# SAU-G0_sheet1.net
KiCad netlist of a schematic drawn in Altium Designer
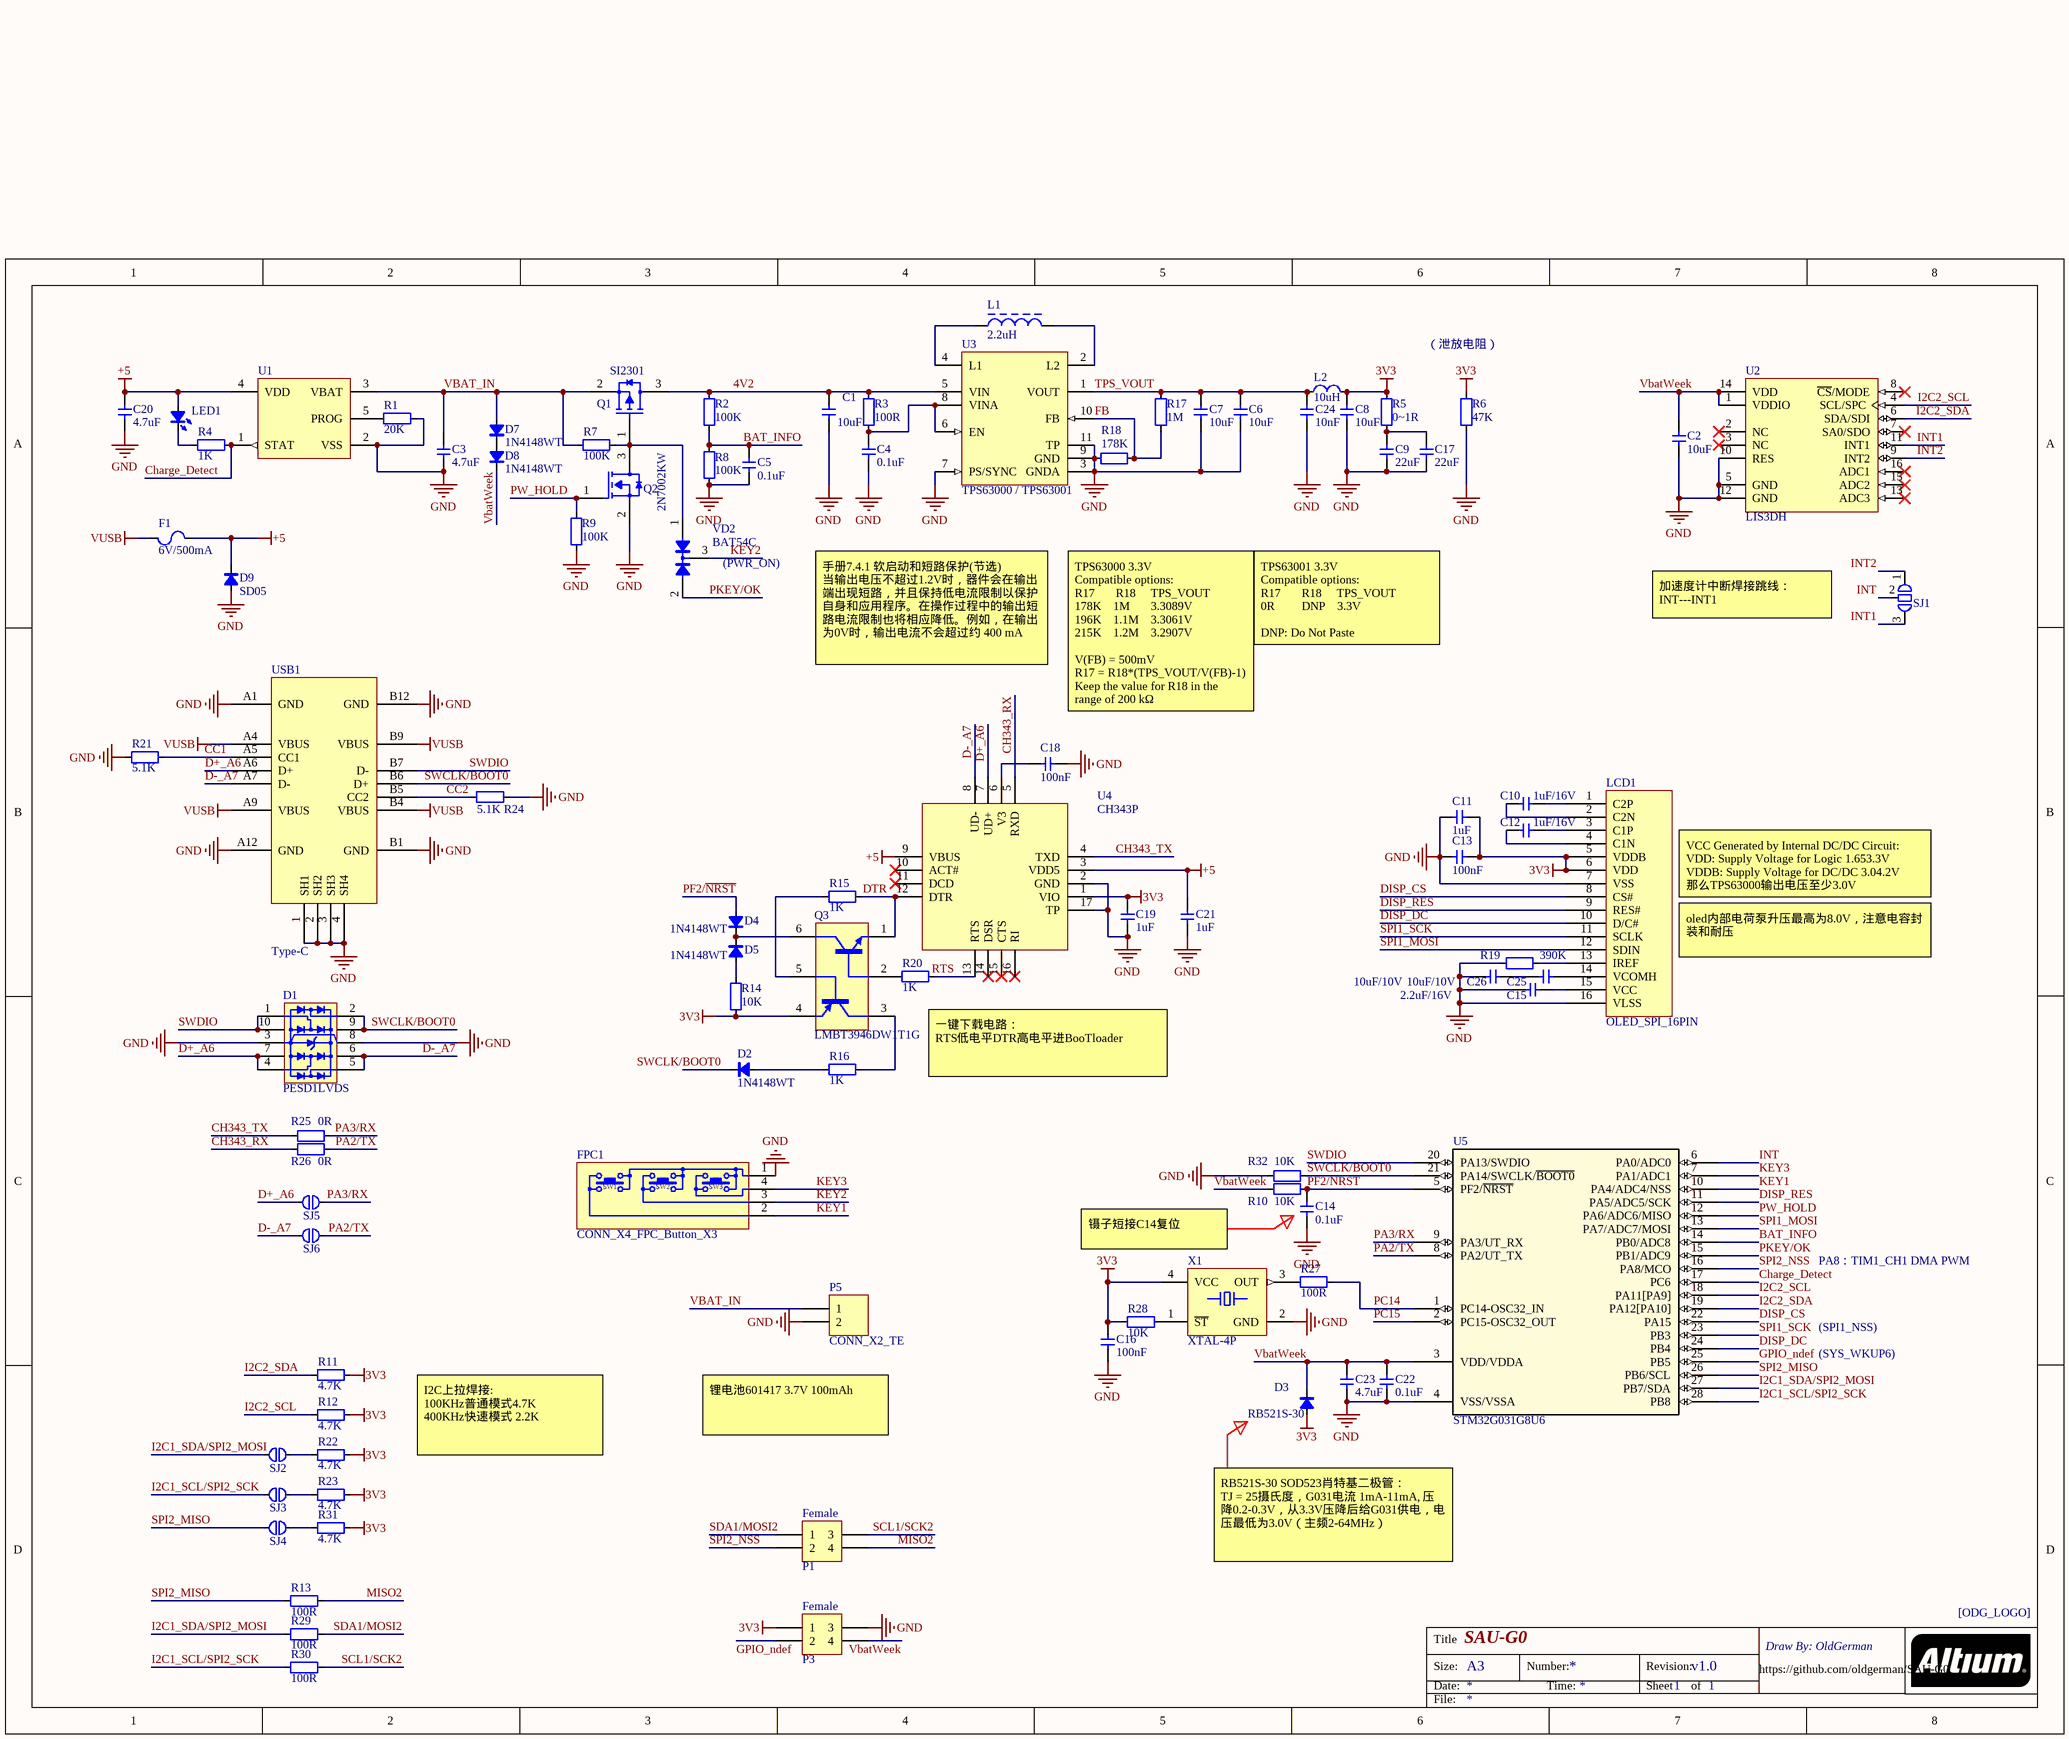
[diagram p0: SAU-G0_sheet1.SchDoc]

(export (version "E")
  (design (tool "Eeschema 10.0.6"))
  (components
    (comp (ref "C1")
      (value "10uF")
      (footprint "C0402")
      (description "Capacitor")
      (libsource (lib "ODG_AD_Lib") (part "CAP"))
    )
    (comp (ref "C2")
      (value "10uF")
      (footprint "C0402")
      (description "Capacitor")
      (libsource (lib "ODG_AD_Lib") (part "CAP"))
    )
    (comp (ref "C3")
      (value "4.7uF")
      (footprint "C0603")
      (description "Capacitor")
      (libsource (lib "ODG_AD_Lib") (part "CAP"))
    )
    (comp (ref "C4")
      (value "0.1uF")
      (footprint "C0402")
      (description "Capacitor")
      (libsource (lib "ODG_AD_Lib") (part "CAP"))
    )
    (comp (ref "C5")
      (value "0.1uF")
      (footprint "C0402")
      (description "Capacitor")
      (libsource (lib "ODG_AD_Lib") (part "CAP"))
    )
    (comp (ref "C6")
      (value "10uF")
      (footprint "C0402")
      (description "Capacitor")
      (libsource (lib "ODG_AD_Lib") (part "CAP"))
    )
    (comp (ref "C7")
      (value "10uF")
      (footprint "C0402")
      (description "Capacitor")
      (libsource (lib "ODG_AD_Lib") (part "CAP"))
    )
    (comp (ref "C8")
      (value "10uF")
      (footprint "C0402")
      (description "Capacitor")
      (libsource (lib "ODG_AD_Lib") (part "CAP"))
    )
    (comp (ref "C9")
      (value "22uF")
      (footprint "C0603")
      (description "Capacitor")
      (libsource (lib "ODG_AD_Lib") (part "CAP"))
    )
    (comp (ref "C10")
      (value "1uF/16V")
      (footprint "C0402")
      (description "Capacitor")
      (libsource (lib "ODG_AD_Lib") (part "CAP"))
    )
    (comp (ref "C11")
      (value "1uF")
      (footprint "C0402")
      (description "Capacitor")
      (libsource (lib "ODG_AD_Lib") (part "CAP"))
    )
    (comp (ref "C12")
      (value "1uF/16V")
      (footprint "C0402")
      (description "Capacitor")
      (libsource (lib "ODG_AD_Lib") (part "CAP"))
    )
    (comp (ref "C13")
      (value "100nF")
      (footprint "C0402")
      (description "Capacitor")
      (libsource (lib "ODG_AD_Lib") (part "CAP"))
    )
    (comp (ref "C14")
      (value "0.1uF")
      (footprint "C0402")
      (description "Capacitor")
      (libsource (lib "ODG_AD_Lib") (part "CAP"))
    )
    (comp (ref "C15")
      (value "2.2uF/16V")
      (footprint "C0603")
      (description "Capacitor")
      (libsource (lib "ODG_AD_Lib") (part "CAP"))
    )
    (comp (ref "C16")
      (value "100nF")
      (footprint "C0402")
      (description "Capacitor")
      (libsource (lib "ODG_AD_Lib") (part "CAP"))
    )
    (comp (ref "C17")
      (value "22uF")
      (footprint "C0603")
      (description "Capacitor")
      (libsource (lib "ODG_AD_Lib") (part "CAP"))
    )
    (comp (ref "C18")
      (value "100nF")
      (footprint "C0402")
      (description "Capacitor")
      (libsource (lib "ODG_AD_Lib") (part "CAP"))
    )
    (comp (ref "C19")
      (value "1uF")
      (footprint "C0402")
      (description "Capacitor")
      (libsource (lib "ODG_AD_Lib") (part "CAP"))
    )
    (comp (ref "C20")
      (value "4.7uF")
      (footprint "C0603")
      (description "Capacitor")
      (libsource (lib "ODG_AD_Lib") (part "CAP"))
    )
    (comp (ref "C21")
      (value "1uF")
      (footprint "C0402")
      (description "Capacitor")
      (libsource (lib "ODG_AD_Lib") (part "CAP"))
    )
    (comp (ref "C22")
      (value "0.1uF")
      (footprint "C0402")
      (description "Capacitor")
      (libsource (lib "ODG_AD_Lib") (part "CAP"))
    )
    (comp (ref "C23")
      (value "4.7uF")
      (footprint "C0402")
      (description "Capacitor")
      (libsource (lib "ODG_AD_Lib") (part "CAP"))
    )
    (comp (ref "C24")
      (value "10nF")
      (footprint "C0402")
      (description "Capacitor")
      (libsource (lib "ODG_AD_Lib") (part "CAP"))
    )
    (comp (ref "C25")
      (value "10uF/10V")
      (footprint "C0402")
      (description "Capacitor")
      (libsource (lib "ODG_AD_Lib") (part "CAP"))
    )
    (comp (ref "C26")
      (value "10uF/10V")
      (footprint "C0402")
      (description "Capacitor")
      (libsource (lib "ODG_AD_Lib") (part "CAP"))
    )
    (comp (ref "D1")
      (value "PESD1LVDS")
      (footprint "DFN2510-10_SOT1165-1")
      (description "Ultra-Low Capacitance TVS Protection")
      (fields (field (name "版权归属") "源创客"))
      (libsource (lib "ODG_AD_Lib") (part "PESD1LVDS"))
    )
    (comp (ref "D2")
      (value "1N4148WT")
      (footprint "SOD-523")
      (description "二极管")
      (libsource (lib "") (part "DIODE_2"))
    )
    (comp (ref "D3")
      (value "RB521S-30")
      (footprint "SOD-523")
      (description "二极管")
      (libsource (lib "") (part "DIODE_1"))
    )
    (comp (ref "D4")
      (value "1N4148WT")
      (footprint "SOD-523")
      (description "二极管")
      (libsource (lib "ODG_AD_Lib") (part "DIODE"))
    )
    (comp (ref "D5")
      (value "1N4148WT")
      (footprint "SOD-523")
      (description "二极管")
      (libsource (lib "") (part "DIODE_3"))
    )
    (comp (ref "D7")
      (value "1N4148WT")
      (footprint "SOD-523")
      (description "二极管")
      (libsource (lib "ODG_AD_Lib") (part "DIODE"))
    )
    (comp (ref "D8")
      (value "1N4148WT")
      (footprint "SOD-523")
      (description "二极管")
      (libsource (lib "ODG_AD_Lib") (part "DIODE"))
    )
    (comp (ref "D9")
      (value "SD05")
      (footprint "SOD-323")
      (description "单向 5V TVS")
      (libsource (lib "") (part "DIODE_1"))
    )
    (comp (ref "F1")
      (value "6V/500mA")
      (footprint "FUSE0603_0.5MM")
      (description "贴片自恢复保险丝")
      (libsource (lib "ODG_AD_Lib") (part "FUSE"))
    )
    (comp (ref "FPC1")
      (value "CONN_X4_FPC_Button_X3")
      (footprint "FPC_Buttons_X3_Flip_to_PCB_Buttom_to_Back_3.06mm_NO_3D_NO_SLIK_1")
      (description "豆老板1.6元车G031电子烟拆机的玩意儿")
      (libsource (lib "ODG_AD_Lib") (part "CONN_X4_FPC_Button_X3"))
    )
    (comp (ref "L1")
      (value "2.2uH")
      (footprint "TAIYO YUDEN MAMK2520T1R0M")
      (libsource (lib "ODG_nRLC_Project") (part "Inductor"))
    )
    (comp (ref "L2")
      (value "10uH")
      (footprint "FER0603")
      (description "贴片叠层电感")
      (libsource (lib "ODG_AD_Lib") (part "inductor_mini"))
    )
    (comp (ref "LCD1")
      (value "OLED_SPI_16PIN")
      (footprint "oled_64x48_0.66_SSD1306_TOP_FPC_to_BACK_1mm_NO_3D_NO_SLIK_1")
      (libsource (lib "ODG_AD_Lib") (part "OLED_SPI_16PIN"))
    )
    (comp (ref "LED1") (value "LED") (footprint "LED0603_WHITE") (libsource (lib "ODG_AD_Lib") (part "LED")))
    (comp (ref "ODG4")
      (value "ODG_LOGO")
      (footprint "ODG_LOGO")
      (libsource (lib "ODG_AD_Lib") (part "ODG_LOGO"))
    )
    (comp (ref "P1")
      (value "Female")
      (footprint "2.0mm_Fmale_2x2")
      (libsource (lib "ODG_AD_Lib") (part "CONN_2X2"))
    )
    (comp (ref "P3")
      (value "Female")
      (footprint "2.0mm_Fmale_2x2")
      (libsource (lib "ODG_AD_Lib") (part "CONN_2X2"))
    )
    (comp (ref "P5")
      (value "CONN_X2_TE")
      (footprint "TE-198181x_Female+Male")
      (description "泰科1981812-1\r\n泰科1981813-1\r\n使用32AWG 特氟龙线外径0.38mm\r\n刺破式")
      (libsource (lib "ODG_AD_Lib") (part "CONN_X2_TE"))
    )
    (comp (ref "Q1")
      (value "SI2301")
      (footprint "INFINEON SOT-23-3")
      (description "P-MOS")
      (libsource (lib "ODG_AD_Lib") (part "P-MOS_123"))
    )
    (comp (ref "Q2")
      (value "2N7002KW")
      (footprint "DIODES SOT-323-3")
      (description "N-MOS")
      (libsource (lib "ODG_AD_Lib") (part "N-MOS_123"))
    )
    (comp (ref "Q3")
      (value "LMBT3946DW1T1G")
      (footprint "ON SEMI SOT-363")
      (description "PNP+NPN, SOT-363")
      (libsource (lib "ODG_AD_Lib") (part "LMBT3946DW1T1G"))
    )
    (comp (ref "R1")
      (value "20K")
      (footprint "R0402")
      (description "Resistor")
      (libsource (lib "") (part "RES_3"))
    )
    (comp (ref "R2")
      (value "100K")
      (footprint "R0402")
      (description "Resistor")
      (libsource (lib "ODG_AD_Lib") (part "RES"))
    )
    (comp (ref "R3")
      (value "100R")
      (footprint "R0402")
      (description "Resistor")
      (libsource (lib "ODG_AD_Lib") (part "RES"))
    )
    (comp (ref "R4")
      (value "1K")
      (footprint "R0402")
      (description "Resistor")
      (libsource (lib "") (part "RES_3"))
    )
    (comp (ref "R5")
      (value "0~1R")
      (footprint "R0402")
      (description "Resistor")
      (libsource (lib "ODG_AD_Lib") (part "RES"))
    )
    (comp (ref "R6")
      (value "47K")
      (footprint "R0603")
      (description "Resistor")
      (libsource (lib "ODG_AD_Lib") (part "RES"))
    )
    (comp (ref "R7")
      (value "100K")
      (footprint "R0402")
      (description "Resistor")
      (libsource (lib "") (part "RES_3"))
    )
    (comp (ref "R8")
      (value "100K")
      (footprint "R0402")
      (description "Resistor")
      (libsource (lib "ODG_AD_Lib") (part "RES"))
    )
    (comp (ref "R9")
      (value "100K")
      (footprint "R0402")
      (description "Resistor")
      (libsource (lib "ODG_AD_Lib") (part "RES"))
    )
    (comp (ref "R10")
      (value "10K")
      (footprint "R0402")
      (description "Resistor")
      (libsource (lib "") (part "RES_2"))
    )
    (comp (ref "R11")
      (value "4.7K")
      (footprint "R0402")
      (description "Resistor")
      (libsource (lib "") (part "RES_2"))
    )
    (comp (ref "R12")
      (value "4.7K")
      (footprint "R0402")
      (description "Resistor")
      (libsource (lib "") (part "RES_2"))
    )
    (comp (ref "R13")
      (value "100R")
      (footprint "R0402")
      (description "Resistor")
      (libsource (lib "") (part "RES_2"))
    )
    (comp (ref "R14")
      (value "10K")
      (footprint "R0402")
      (description "Resistor")
      (libsource (lib "") (part "RES_1"))
    )
    (comp (ref "R15")
      (value "1K")
      (footprint "R0402")
      (description "Resistor")
      (libsource (lib "ODG_AD_Lib") (part "RES"))
    )
    (comp (ref "R16")
      (value "1K")
      (footprint "R0402")
      (description "Resistor")
      (libsource (lib "ODG_AD_Lib") (part "RES"))
    )
    (comp (ref "R17")
      (value "1M")
      (footprint "R0402")
      (description "Resistor")
      (libsource (lib "ODG_AD_Lib") (part "RES"))
    )
    (comp (ref "R18")
      (value "178K")
      (footprint "R0402")
      (description "Resistor")
      (libsource (lib "") (part "RES_3"))
    )
    (comp (ref "R19")
      (value "390K")
      (footprint "R0402")
      (description "Resistor")
      (libsource (lib "") (part "RES_1"))
    )
    (comp (ref "R20")
      (value "1K")
      (footprint "R0402")
      (description "Resistor")
      (libsource (lib "") (part "RES_2"))
    )
    (comp (ref "R21")
      (value "5.1K")
      (footprint "R0402")
      (description "Resistor")
      (libsource (lib "") (part "RES_3"))
    )
    (comp (ref "R22")
      (value "4.7K")
      (footprint "R0402")
      (description "Resistor")
      (libsource (lib "") (part "RES_2"))
    )
    (comp (ref "R23")
      (value "4.7K")
      (footprint "R0402")
      (description "Resistor")
      (libsource (lib "") (part "RES_2"))
    )
    (comp (ref "R24")
      (value "5.1K")
      (footprint "R0402")
      (description "Resistor")
      (libsource (lib "") (part "RES_2"))
    )
    (comp (ref "R25")
      (value "0R")
      (footprint "R0402")
      (description "Resistor")
      (libsource (lib "") (part "RES_1"))
    )
    (comp (ref "R26")
      (value "0R")
      (footprint "R0402")
      (description "Resistor")
      (libsource (lib "") (part "RES_1"))
    )
    (comp (ref "R27")
      (value "100R")
      (footprint "R0402")
      (description "Resistor")
      (libsource (lib "") (part "RES_2"))
    )
    (comp (ref "R28")
      (value "10K")
      (footprint "R0402")
      (description "Resistor")
      (libsource (lib "") (part "RES_2"))
    )
    (comp (ref "R29")
      (value "100R")
      (footprint "R0402")
      (description "Resistor")
      (libsource (lib "") (part "RES_2"))
    )
    (comp (ref "R30")
      (value "100R")
      (footprint "R0402")
      (description "Resistor")
      (libsource (lib "") (part "RES_2"))
    )
    (comp (ref "R31")
      (value "4.7K")
      (footprint "R0402")
      (description "Resistor")
      (libsource (lib "") (part "RES_2"))
    )
    (comp (ref "R32")
      (value "10K")
      (footprint "R0402")
      (description "Resistor")
      (libsource (lib "ODG_AD_Lib") (part "RES"))
    )
    (comp (ref "SJ1")
      (value "SJ_3P")
      (footprint "SJ_3P_MINI")
      (description "焊接跳线二选一")
      (libsource (lib "ODG_AD_Lib") (part "SJ_3P"))
    )
    (comp (ref "SJ2")
      (value "SJ_2P")
      (footprint "SJ_2P_TINY")
      (description "焊接跳线")
      (libsource (lib "ODG_AD_Lib") (part "SJ_2P"))
    )
    (comp (ref "SJ3")
      (value "SJ_2P")
      (footprint "SJ_2P_TINY")
      (description "焊接跳线")
      (libsource (lib "ODG_AD_Lib") (part "SJ_2P"))
    )
    (comp (ref "SJ4")
      (value "SJ_2P")
      (footprint "SJ_2P_TINY")
      (description "焊接跳线")
      (libsource (lib "ODG_AD_Lib") (part "SJ_2P"))
    )
    (comp (ref "SJ5")
      (value "SJ_2P")
      (footprint "SJ_2P_TINY")
      (description "焊接跳线")
      (libsource (lib "ODG_AD_Lib") (part "SJ_2P"))
    )
    (comp (ref "SJ6")
      (value "SJ_2P")
      (footprint "SJ_2P_TINY")
      (description "焊接跳线")
      (libsource (lib "ODG_AD_Lib") (part "SJ_2P"))
    )
    (comp (ref "U1")
      (value "MCP73831T")
      (footprint "MICROCHIP SOT-23-5 OT")
      (libsource (lib "ODG_AD_Lib") (part "MCP73831T"))
    )
    (comp (ref "U2") (value "LIS3DH") (footprint "LGA-16-3X3") (libsource (lib "ODG_AD_Lib") (part "LIS3DH")))
    (comp (ref "U3")
      (value "TPS63000 / TPS63001")
      (footprint "TI PVSON-10 3x3MM DRC")
      (description "Buck-Boost Converter\r\n具有 1.8A 电流开关并采用 3x3 QFN 封装的高效率降压/升压转换器")
      (libsource (lib "ODG_Project") (part "TPS63000"))
    )
    (comp (ref "U4")
      (value "CH343P")
      (footprint "CH343P_QFN-16 3x3MM")
      (description "usb to ttl")
      (libsource (lib "ODG_AD_Lib") (part "CH343P"))
    )
    (comp (ref "U5")
      (value "STM32G031G8U6")
      (footprint "UFQFPN28-4x4mm_ODG")
      (description "No Description Available")
      (fields (field (name "COPYRIGHT") "Copyright (C) 2022 Ultra Librarian. All rights reserved."))
      (libsource (lib "ODG_AD_Lib") (part "STM32G031G8U6"))
    )
    (comp (ref "USB1")
      (value "Type-C")
      (footprint "TYPE-C_14P_Vertical_H_10mm")
      (libsource (lib "ODG_AD_Lib") (part "USB-Type-C_14P"))
    )
    (comp (ref "VD2")
      (value "BAT54C")
      (footprint "DIODES SOT-323-3")
      (description "贴片肖特基二极管")
      (fields (field (name "版权归属") "源创客"))
      (libsource (lib "ODG_Project") (part "BAT54C"))
    )
    (comp (ref "X1")
      (value "XTAL-4P")
      (footprint "NDK NX2520SA")
      (description "4脚有源晶振")
      (fields (field (name "版权归属") "源创客"))
      (libsource (lib "ODG_AD_Lib") (part "XTAL-4P_oscillator"))
    )
  )
  (nets
    (net (code "1") (name "+5") (class "Default")
      (node (ref "C20") (pin "1") (pinfunction "1_1") (pintype "passive"))
      (node (ref "C21") (pin "2") (pinfunction "2_2") (pintype "passive"))
      (node (ref "D9") (pin "2") (pinfunction "C_2") (pintype "passive"))
      (node (ref "F1") (pin "2") (pinfunction "2_2") (pintype "passive"))
      (node (ref "LED1") (pin "1") (pinfunction "A_1") (pintype "passive"))
      (node (ref "U1") (pin "4") (pinfunction "VDD_4") (pintype "power_in"))
      (node (ref "U4") (pin "3") (pinfunction "VDD5_3") (pintype "passive"))
      (node (ref "U4") (pin "9") (pinfunction "VBUS_9") (pintype "passive"))
    )
    (net (code "2") (name "/4V2") (class "Default")
      (node (ref "C1") (pin "1") (pinfunction "1_1") (pintype "passive"))
      (node (ref "Q1") (pin "3") (pinfunction "D_3") (pintype "passive"))
      (node (ref "R2") (pin "2") (pinfunction "2_2") (pintype "passive"))
      (node (ref "R3") (pin "2") (pinfunction "2_2") (pintype "passive"))
      (node (ref "U3") (pin "5") (pinfunction "VIN_5") (pintype "passive"))
    )
    (net (code "3") (name "/BAT_INFO") (class "Default")
      (node (ref "C5") (pin "1") (pinfunction "1_1") (pintype "passive"))
      (node (ref "R2") (pin "1") (pinfunction "1_1") (pintype "passive"))
      (node (ref "R8") (pin "2") (pinfunction "2_2") (pintype "passive"))
      (node (ref "U5") (pin "14") (pinfunction "PB0/ADC8_14") (pintype "bidirectional"))
    )
    (net (code "4") (name "/CC1") (class "Default")
      (node (ref "R21") (pin "1") (pinfunction "1_1") (pintype "passive"))
      (node (ref "USB1") (pin "A5") (pinfunction "CC1_A5") (pintype "passive"))
    )
    (net (code "5") (name "/CC2") (class "Default")
      (node (ref "R24") (pin "2") (pinfunction "2_2") (pintype "passive"))
      (node (ref "USB1") (pin "B5") (pinfunction "CC2_B5") (pintype "passive"))
    )
    (net (code "6") (name "/CH343_RX") (class "Default")
      (node (ref "R26") (pin "1") (pinfunction "1_1") (pintype "passive"))
      (node (ref "U4") (pin "5") (pinfunction "RXD_5") (pintype "passive"))
    )
    (net (code "7") (name "/CH343_TX") (class "Default")
      (node (ref "R25") (pin "1") (pinfunction "1_1") (pintype "passive"))
      (node (ref "U4") (pin "4") (pinfunction "TXD_4") (pintype "passive"))
    )
    (net (code "8") (name "/Charge_Detect") (class "Default")
      (node (ref "R4") (pin "1") (pinfunction "1_1") (pintype "passive"))
      (node (ref "U1") (pin "1") (pinfunction "STAT_1") (pintype "output"))
      (node (ref "U5") (pin "17") (pinfunction "PC6_17") (pintype "bidirectional"))
    )
    (net (code "9") (name "/D+_A6") (class "Default")
      (node (ref "D1") (pin "4") (pinfunction "I/O_4") (pintype "passive"))
      (node (ref "D1") (pin "7") (pinfunction "GND_7") (pintype "passive"))
      (node (ref "SJ5") (pin "1") (pinfunction "1_1") (pintype "passive"))
      (node (ref "U4") (pin "7") (pinfunction "UD+_7") (pintype "passive"))
      (node (ref "USB1") (pin "A6") (pinfunction "D+_A6") (pintype "passive"))
    )
    (net (code "10") (name "/D-_A7") (class "Default")
      (node (ref "D1") (pin "5") (pinfunction "I/O_5") (pintype "passive"))
      (node (ref "D1") (pin "6") (pinfunction "GND_6") (pintype "passive"))
      (node (ref "SJ6") (pin "1") (pinfunction "1_1") (pintype "passive"))
      (node (ref "U4") (pin "8") (pinfunction "UD-_8") (pintype "passive"))
      (node (ref "USB1") (pin "A7") (pinfunction "D-_A7") (pintype "passive"))
    )
    (net (code "11") (name "/DISP_CS") (class "Default")
      (node (ref "LCD1") (pin "8") (pinfunction "CS#_8") (pintype "passive"))
      (node (ref "U5") (pin "22") (pinfunction "PA15_22") (pintype "bidirectional"))
    )
    (net (code "12") (name "/DISP_DC") (class "Default")
      (node (ref "LCD1") (pin "10") (pinfunction "D/C#_10") (pintype "passive"))
      (node (ref "U5") (pin "24") (pinfunction "PB4_24") (pintype "bidirectional"))
    )
    (net (code "13") (name "/DISP_RES") (class "Default")
      (node (ref "LCD1") (pin "9") (pinfunction "RES#_9") (pintype "passive"))
      (node (ref "U5") (pin "11") (pinfunction "PA5/ADC5/SCK_11") (pintype "bidirectional"))
    )
    (net (code "14") (name "/DTR") (class "Default")
      (node (ref "Q3") (pin "1") (pinfunction "E_1") (pintype "passive"))
      (node (ref "R15") (pin "2") (pinfunction "2_2") (pintype "passive"))
      (node (ref "U4") (pin "12") (pinfunction "DTR_12") (pintype "passive"))
    )
    (net (code "15") (name "/FB") (class "Default")
      (node (ref "R17") (pin "1") (pinfunction "1_1") (pintype "passive"))
      (node (ref "R18") (pin "1") (pinfunction "1_1") (pintype "passive"))
      (node (ref "U3") (pin "10") (pinfunction "FB_10") (pintype "input"))
    )
    (net (code "16") (name "/GPIO_ndef") (class "Default")
      (node (ref "P3") (pin "2") (pinfunction "2_2") (pintype "passive"))
      (node (ref "U5") (pin "25") (pinfunction "PB5_25") (pintype "bidirectional"))
    )
    (net (code "17") (name "/I2C1_SCL{slash}SPI2_SCK") (class "Default")
      (node (ref "R30") (pin "2") (pinfunction "2_2") (pintype "passive"))
      (node (ref "SJ3") (pin "1") (pinfunction "1_1") (pintype "passive"))
      (node (ref "U5") (pin "28") (pinfunction "PB8_28") (pintype "bidirectional"))
    )
    (net (code "18") (name "/I2C1_SDA{slash}SPI2_MOSI") (class "Default")
      (node (ref "R29") (pin "2") (pinfunction "2_2") (pintype "passive"))
      (node (ref "SJ2") (pin "1") (pinfunction "1_1") (pintype "passive"))
      (node (ref "U5") (pin "27") (pinfunction "PB7/SDA_27") (pintype "bidirectional"))
    )
    (net (code "19") (name "/I2C2_SCL") (class "Default")
      (node (ref "R12") (pin "2") (pinfunction "2_2") (pintype "passive"))
      (node (ref "U2") (pin "4") (pinfunction "SCL/SPC_4") (pintype "input"))
      (node (ref "U5") (pin "18") (pinfunction "PA11[PA9]_18") (pintype "bidirectional"))
    )
    (net (code "20") (name "/I2C2_SDA") (class "Default")
      (node (ref "R11") (pin "2") (pinfunction "2_2") (pintype "passive"))
      (node (ref "U2") (pin "6") (pinfunction "SDA/SDI_6") (pintype "bidirectional"))
      (node (ref "U5") (pin "19") (pinfunction "PA12[PA10]_19") (pintype "bidirectional"))
    )
    (net (code "21") (name "/INT") (class "Default")
      (node (ref "SJ1") (pin "2") (pinfunction "2_2") (pintype "passive"))
      (node (ref "U5") (pin "6") (pinfunction "PA0/ADC0_6") (pintype "bidirectional"))
    )
    (net (code "22") (name "/INT1") (class "Default")
      (node (ref "SJ1") (pin "3") (pinfunction "3_3") (pintype "passive"))
      (node (ref "U2") (pin "11") (pinfunction "INT1_11") (pintype "bidirectional"))
    )
    (net (code "23") (name "/INT2") (class "Default")
      (node (ref "SJ1") (pin "1") (pinfunction "1_1") (pintype "passive"))
      (node (ref "U2") (pin "9") (pinfunction "INT2_9") (pintype "bidirectional"))
    )
    (net (code "24") (name "/KEY1") (class "Default")
      (node (ref "FPC1") (pin "2") (pinfunction "2_2") (pintype "passive"))
      (node (ref "U5") (pin "10") (pinfunction "PA4/ADC4/NSS_10") (pintype "bidirectional"))
    )
    (net (code "25") (name "/KEY2") (class "Default")
      (node (ref "FPC1") (pin "3") (pinfunction "3_3") (pintype "passive"))
      (node (ref "VD2") (pin "3") (pinfunction "3_3") (pintype "passive"))
    )
    (net (code "26") (name "/KEY3") (class "Default")
      (node (ref "FPC1") (pin "4") (pinfunction "4_4") (pintype "passive"))
      (node (ref "U5") (pin "7") (pinfunction "PA1/ADC1_7") (pintype "bidirectional"))
    )
    (net (code "27") (name "/MISO2") (class "Default")
      (node (ref "P1") (pin "4") (pinfunction "4_4") (pintype "passive"))
      (node (ref "R13") (pin "1") (pinfunction "1_1") (pintype "passive"))
    )
    (net (code "28") (name "/PA2{slash}TX") (class "Default")
      (node (ref "R26") (pin "2") (pinfunction "2_2") (pintype "passive"))
      (node (ref "SJ6") (pin "2") (pinfunction "2_2") (pintype "passive"))
      (node (ref "U5") (pin "8") (pinfunction "PA2/UT_TX_8") (pintype "bidirectional"))
    )
    (net (code "29") (name "/PA3{slash}RX") (class "Default")
      (node (ref "R25") (pin "2") (pinfunction "2_2") (pintype "passive"))
      (node (ref "SJ5") (pin "2") (pinfunction "2_2") (pintype "passive"))
      (node (ref "U5") (pin "9") (pinfunction "PA3/UT_RX_9") (pintype "bidirectional"))
    )
    (net (code "30") (name "/PC14") (class "Default")
      (node (ref "R27") (pin "1") (pinfunction "1_1") (pintype "passive"))
      (node (ref "U5") (pin "1") (pinfunction "PC14-OSC32_IN_1") (pintype "bidirectional"))
    )
    (net (code "31") (name "/PC15") (class "Default")
      (node (ref "U5") (pin "2") (pinfunction "PC15-OSC32_OUT_2") (pintype "bidirectional"))
    )
    (net (code "32") (name "/PF2{slash}~{NRST}") (class "Default")
      (node (ref "C14") (pin "1") (pinfunction "1_1") (pintype "passive"))
      (node (ref "D4") (pin "1") (pinfunction "A_1") (pintype "passive"))
      (node (ref "R10") (pin "1") (pinfunction "1_1") (pintype "passive"))
      (node (ref "U5") (pin "5") (pinfunction "PF2/~{NRST}_5") (pintype "bidirectional"))
    )
    (net (code "33") (name "/PKEY{slash}OK") (class "Default")
      (node (ref "U5") (pin "15") (pinfunction "PB1/ADC9_15") (pintype "bidirectional"))
      (node (ref "VD2") (pin "2") (pinfunction "2_2") (pintype "passive"))
    )
    (net (code "34") (name "/PW_HOLD") (class "Default")
      (node (ref "Q2") (pin "1") (pinfunction "G_1") (pintype "passive"))
      (node (ref "R9") (pin "2") (pinfunction "2_2") (pintype "passive"))
      (node (ref "U5") (pin "12") (pinfunction "PA6/ADC6/MISO_12") (pintype "bidirectional"))
    )
    (net (code "35") (name "/RTS") (class "Default")
      (node (ref "R20") (pin "1") (pinfunction "1_1") (pintype "passive"))
      (node (ref "U4") (pin "13") (pinfunction "RTS_13") (pintype "passive"))
    )
    (net (code "36") (name "/SCL1{slash}SCK2") (class "Default")
      (node (ref "P1") (pin "3") (pinfunction "3_3") (pintype "passive"))
      (node (ref "R30") (pin "1") (pinfunction "1_1") (pintype "passive"))
    )
    (net (code "37") (name "/SDA1{slash}MOSI2") (class "Default")
      (node (ref "P1") (pin "1") (pinfunction "1_1") (pintype "passive"))
      (node (ref "R29") (pin "1") (pinfunction "1_1") (pintype "passive"))
    )
    (net (code "38") (name "/SPI1_MOSI") (class "Default")
      (node (ref "LCD1") (pin "12") (pinfunction "SDIN_12") (pintype "passive"))
      (node (ref "U5") (pin "13") (pinfunction "PA7/ADC7/MOSI_13") (pintype "bidirectional"))
    )
    (net (code "39") (name "/SPI1_SCK") (class "Default")
      (node (ref "LCD1") (pin "11") (pinfunction "SCLK_11") (pintype "passive"))
      (node (ref "U5") (pin "23") (pinfunction "PB3_23") (pintype "bidirectional"))
    )
    (net (code "40") (name "/SPI2_MISO") (class "Default")
      (node (ref "R13") (pin "2") (pinfunction "2_2") (pintype "passive"))
      (node (ref "SJ4") (pin "1") (pinfunction "1_1") (pintype "passive"))
      (node (ref "U5") (pin "26") (pinfunction "PB6/SCL_26") (pintype "bidirectional"))
    )
    (net (code "41") (name "/SPI2_NSS") (class "Default")
      (node (ref "P1") (pin "2") (pinfunction "2_2") (pintype "passive"))
      (node (ref "U5") (pin "16") (pinfunction "PA8/MCO_16") (pintype "bidirectional"))
    )
    (net (code "42") (name "/SWCLK{slash}BOOT0") (class "Default")
      (node (ref "D1") (pin "2") (pinfunction "I/O_2") (pintype "passive"))
      (node (ref "D1") (pin "9") (pinfunction "GND_9") (pintype "passive"))
      (node (ref "D2") (pin "2") (pinfunction "C_2") (pintype "passive"))
      (node (ref "R32") (pin "2") (pinfunction "2_2") (pintype "passive"))
      (node (ref "U5") (pin "21") (pinfunction "PA14/SWCLK/~{BOOT0}_21") (pintype "bidirectional"))
      (node (ref "USB1") (pin "B6") (pinfunction "D+_B6") (pintype "passive"))
    )
    (net (code "43") (name "/SWDIO") (class "Default")
      (node (ref "D1") (pin "1") (pinfunction "I/O_1") (pintype "passive"))
      (node (ref "D1") (pin "10") (pinfunction "GND_10") (pintype "passive"))
      (node (ref "U5") (pin "20") (pinfunction "PA13/SWDIO_20") (pintype "bidirectional"))
      (node (ref "USB1") (pin "B7") (pinfunction "D-_B7") (pintype "passive"))
    )
    (net (code "44") (name "/TPS_VOUT") (class "Default")
      (node (ref "C24") (pin "1") (pinfunction "1_1") (pintype "passive"))
      (node (ref "C6") (pin "1") (pinfunction "1_1") (pintype "passive"))
      (node (ref "C7") (pin "1") (pinfunction "1_1") (pintype "passive"))
      (node (ref "L2") (pin "1") (pinfunction "1_1") (pintype "passive"))
      (node (ref "R17") (pin "2") (pinfunction "2_2") (pintype "passive"))
      (node (ref "U3") (pin "1") (pinfunction "VOUT_1") (pintype "passive"))
    )
    (net (code "45") (name "/VBAT_IN") (class "Default")
      (node (ref "C3") (pin "1") (pinfunction "1_1") (pintype "passive"))
      (node (ref "D7") (pin "1") (pinfunction "A_1") (pintype "passive"))
      (node (ref "P5") (pin "1") (pinfunction "1_1") (pintype "passive"))
      (node (ref "Q1") (pin "2") (pinfunction "S_2") (pintype "passive"))
      (node (ref "R7") (pin "2") (pinfunction "2_2") (pintype "passive"))
      (node (ref "U1") (pin "3") (pinfunction "VBAT_3") (pintype "power_in"))
    )
    (net (code "46") (name "/VbatWeek") (class "Default")
      (node (ref "C2") (pin "1") (pinfunction "1_1") (pintype "passive"))
      (node (ref "C22") (pin "1") (pinfunction "1_1") (pintype "passive"))
      (node (ref "C23") (pin "1") (pinfunction "1_1") (pintype "passive"))
      (node (ref "D3") (pin "2") (pinfunction "C_2") (pintype "passive"))
      (node (ref "D8") (pin "2") (pinfunction "C_2") (pintype "passive"))
      (node (ref "P3") (pin "4") (pinfunction "4_4") (pintype "passive"))
      (node (ref "R10") (pin "2") (pinfunction "2_2") (pintype "passive"))
      (node (ref "U2") (pin "1") (pinfunction "VDDIO_1") (pintype "power_in"))
      (node (ref "U2") (pin "14") (pinfunction "VDD_14") (pintype "power_in"))
      (node (ref "U5") (pin "3") (pinfunction "VDD/VDDA_3") (pintype "power_in"))
    )
    (net (code "47") (name "3V3") (class "Default")
      (node (ref "C11") (pin "1") (pinfunction "1_1") (pintype "passive"))
      (node (ref "C13") (pin "2") (pinfunction "2_2") (pintype "passive"))
      (node (ref "C16") (pin "1") (pinfunction "1_1") (pintype "passive"))
      (node (ref "C19") (pin "2") (pinfunction "2_2") (pintype "passive"))
      (node (ref "C8") (pin "1") (pinfunction "1_1") (pintype "passive"))
      (node (ref "D3") (pin "1") (pinfunction "A_1") (pintype "passive"))
      (node (ref "L2") (pin "2") (pinfunction "2_2") (pintype "passive"))
      (node (ref "LCD1") (pin "5") (pinfunction "VDDB_5") (pintype "passive"))
      (node (ref "LCD1") (pin "6") (pinfunction "VDD_6") (pintype "passive"))
      (node (ref "P3") (pin "1") (pinfunction "1_1") (pintype "passive"))
      (node (ref "Q3") (pin "4") (pinfunction "E_4") (pintype "passive"))
      (node (ref "R11") (pin "1") (pinfunction "1_1") (pintype "passive"))
      (node (ref "R12") (pin "1") (pinfunction "1_1") (pintype "passive"))
      (node (ref "R14") (pin "1") (pinfunction "1_1") (pintype "passive"))
      (node (ref "R22") (pin "1") (pinfunction "1_1") (pintype "passive"))
      (node (ref "R23") (pin "1") (pinfunction "1_1") (pintype "passive"))
      (node (ref "R28") (pin "2") (pinfunction "2_2") (pintype "passive"))
      (node (ref "R31") (pin "1") (pinfunction "1_1") (pintype "passive"))
      (node (ref "R5") (pin "2") (pinfunction "2_2") (pintype "passive"))
      (node (ref "R6") (pin "2") (pinfunction "2_2") (pintype "passive"))
      (node (ref "U4") (pin "1") (pinfunction "VIO_1") (pintype "passive"))
      (node (ref "X1") (pin "4") (pinfunction "VCC_4") (pintype "passive"))
    )
    (net (code "48") (name "GND") (class "Default")
      (node (ref "C1") (pin "2") (pinfunction "2_2") (pintype "passive"))
      (node (ref "C11") (pin "2") (pinfunction "2_2") (pintype "passive"))
      (node (ref "C13") (pin "1") (pinfunction "1_1") (pintype "passive"))
      (node (ref "C14") (pin "2") (pinfunction "2_2") (pintype "passive"))
      (node (ref "C15") (pin "2") (pinfunction "2_2") (pintype "passive"))
      (node (ref "C16") (pin "2") (pinfunction "2_2") (pintype "passive"))
      (node (ref "C17") (pin "2") (pinfunction "2_2") (pintype "passive"))
      (node (ref "C18") (pin "2") (pinfunction "2_2") (pintype "passive"))
      (node (ref "C19") (pin "1") (pinfunction "1_1") (pintype "passive"))
      (node (ref "C2") (pin "2") (pinfunction "2_2") (pintype "passive"))
      (node (ref "C20") (pin "2") (pinfunction "2_2") (pintype "passive"))
      (node (ref "C21") (pin "1") (pinfunction "1_1") (pintype "passive"))
      (node (ref "C22") (pin "2") (pinfunction "2_2") (pintype "passive"))
      (node (ref "C23") (pin "2") (pinfunction "2_2") (pintype "passive"))
      (node (ref "C24") (pin "2") (pinfunction "2_2") (pintype "passive"))
      (node (ref "C26") (pin "2") (pinfunction "2_2") (pintype "passive"))
      (node (ref "C3") (pin "2") (pinfunction "2_2") (pintype "passive"))
      (node (ref "C4") (pin "2") (pinfunction "2_2") (pintype "passive"))
      (node (ref "C5") (pin "2") (pinfunction "2_2") (pintype "passive"))
      (node (ref "C6") (pin "2") (pinfunction "2_2") (pintype "passive"))
      (node (ref "C7") (pin "2") (pinfunction "2_2") (pintype "passive"))
      (node (ref "C8") (pin "2") (pinfunction "2_2") (pintype "passive"))
      (node (ref "C9") (pin "2") (pinfunction "2_2") (pintype "passive"))
      (node (ref "D1") (pin "3") (pinfunction "GND_3") (pintype "passive"))
      (node (ref "D1") (pin "8") (pinfunction "GND_8") (pintype "passive"))
      (node (ref "D9") (pin "1") (pinfunction "A_1") (pintype "passive"))
      (node (ref "FPC1") (pin "1") (pinfunction "1_1") (pintype "passive"))
      (node (ref "LCD1") (pin "16") (pinfunction "VLSS_16") (pintype "passive"))
      (node (ref "LCD1") (pin "7") (pinfunction "VSS_7") (pintype "passive"))
      (node (ref "P3") (pin "3") (pinfunction "3_3") (pintype "passive"))
      (node (ref "P5") (pin "2") (pinfunction "2_2") (pintype "passive"))
      (node (ref "Q2") (pin "2") (pinfunction "S_2") (pintype "passive"))
      (node (ref "R1") (pin "1") (pinfunction "1_1") (pintype "passive"))
      (node (ref "R18") (pin "2") (pinfunction "2_2") (pintype "passive"))
      (node (ref "R19") (pin "1") (pinfunction "1_1") (pintype "passive"))
      (node (ref "R21") (pin "2") (pinfunction "2_2") (pintype "passive"))
      (node (ref "R24") (pin "1") (pinfunction "1_1") (pintype "passive"))
      (node (ref "R32") (pin "1") (pinfunction "1_1") (pintype "passive"))
      (node (ref "R6") (pin "1") (pinfunction "1_1") (pintype "passive"))
      (node (ref "R8") (pin "1") (pinfunction "1_1") (pintype "passive"))
      (node (ref "R9") (pin "1") (pinfunction "1_1") (pintype "passive"))
      (node (ref "U1") (pin "2") (pinfunction "VSS_2") (pintype "power_in"))
      (node (ref "U2") (pin "10") (pinfunction "RES_10") (pintype "power_in"))
      (node (ref "U2") (pin "12") (pinfunction "GND_12") (pintype "power_in"))
      (node (ref "U2") (pin "5") (pinfunction "GND_5") (pintype "power_in"))
      (node (ref "U3") (pin "11") (pinfunction "TP_11") (pintype "passive"))
      (node (ref "U3") (pin "3") (pinfunction "GNDA_3") (pintype "passive"))
      (node (ref "U3") (pin "7") (pinfunction "PS/SYNC_7") (pintype "input"))
      (node (ref "U3") (pin "9") (pinfunction "GND_9") (pintype "passive"))
      (node (ref "U4") (pin "17") (pinfunction "TP_17") (pintype "passive"))
      (node (ref "U4") (pin "2") (pinfunction "GND_2") (pintype "passive"))
      (node (ref "U5") (pin "4") (pinfunction "VSS/VSSA_4") (pintype "power_in"))
      (node (ref "USB1") (pin "1") (pinfunction "SH1_1") (pintype "passive"))
      (node (ref "USB1") (pin "2") (pinfunction "SH2_2") (pintype "passive"))
      (node (ref "USB1") (pin "3") (pinfunction "SH3_3") (pintype "passive"))
      (node (ref "USB1") (pin "4") (pinfunction "SH4_4") (pintype "passive"))
      (node (ref "USB1") (pin "A1") (pinfunction "GND_A1") (pintype "passive"))
      (node (ref "USB1") (pin "A12") (pinfunction "GND_A12") (pintype "passive"))
      (node (ref "USB1") (pin "B1") (pinfunction "GND_B1") (pintype "passive"))
      (node (ref "USB1") (pin "B12") (pinfunction "GND_B12") (pintype "passive"))
      (node (ref "X1") (pin "2") (pinfunction "GND_2") (pintype "passive"))
    )
    (net (code "49") (name "Net-(C17-Pad1)") (class "Default")
      (node (ref "C17") (pin "1") (pinfunction "1_1") (pintype "passive"))
      (node (ref "C9") (pin "1") (pinfunction "1_1") (pintype "passive"))
      (node (ref "R5") (pin "1") (pinfunction "1_1") (pintype "passive"))
    )
    (net (code "50") (name "Net-(C25-Pad2)") (class "Default")
      (node (ref "C25") (pin "2") (pinfunction "2_2") (pintype "passive"))
      (node (ref "C26") (pin "1") (pinfunction "1_1") (pintype "passive"))
    )
    (net (code "51") (name "Net-(D2-A)") (class "Default")
      (node (ref "D2") (pin "1") (pinfunction "A_1") (pintype "passive"))
      (node (ref "R16") (pin "1") (pinfunction "1_1") (pintype "passive"))
    )
    (net (code "52") (name "Net-(D4-C)") (class "Default")
      (node (ref "D4") (pin "2") (pinfunction "C_2") (pintype "passive"))
      (node (ref "D5") (pin "2") (pinfunction "C_2") (pintype "passive"))
      (node (ref "Q3") (pin "6") (pinfunction "C_6") (pintype "passive"))
    )
    (net (code "53") (name "Net-(D5-A)") (class "Default")
      (node (ref "D5") (pin "1") (pinfunction "A_1") (pintype "passive"))
      (node (ref "R14") (pin "2") (pinfunction "2_2") (pintype "passive"))
    )
    (net (code "54") (name "Net-(D7-C)") (class "Default")
      (node (ref "D7") (pin "2") (pinfunction "C_2") (pintype "passive"))
      (node (ref "D8") (pin "1") (pinfunction "A_1") (pintype "passive"))
    )
    (net (code "55") (name "Net-(LCD1-C1N)") (class "Default")
      (node (ref "C12") (pin "2") (pinfunction "2_2") (pintype "passive"))
      (node (ref "LCD1") (pin "4") (pinfunction "C1N_4") (pintype "passive"))
    )
    (net (code "56") (name "Net-(LCD1-C1P)") (class "Default")
      (node (ref "C12") (pin "1") (pinfunction "1_1") (pintype "passive"))
      (node (ref "LCD1") (pin "3") (pinfunction "C1P_3") (pintype "passive"))
    )
    (net (code "57") (name "Net-(LCD1-C2N)") (class "Default")
      (node (ref "C10") (pin "2") (pinfunction "2_2") (pintype "passive"))
      (node (ref "LCD1") (pin "2") (pinfunction "C2N_2") (pintype "passive"))
    )
    (net (code "58") (name "Net-(LCD1-C2P)") (class "Default")
      (node (ref "C10") (pin "1") (pinfunction "1_1") (pintype "passive"))
      (node (ref "LCD1") (pin "1") (pinfunction "C2P_1") (pintype "passive"))
    )
    (net (code "59") (name "Net-(LCD1-IREF)") (class "Default")
      (node (ref "LCD1") (pin "13") (pinfunction "IREF_13") (pintype "passive"))
      (node (ref "R19") (pin "2") (pinfunction "2_2") (pintype "passive"))
    )
    (net (code "60") (name "Net-(LCD1-VCC)") (class "Default")
      (node (ref "C15") (pin "1") (pinfunction "1_1") (pintype "passive"))
      (node (ref "LCD1") (pin "15") (pinfunction "VCC_15") (pintype "passive"))
    )
    (net (code "61") (name "Net-(LCD1-VCOMH)") (class "Default")
      (node (ref "C25") (pin "1") (pinfunction "1_1") (pintype "passive"))
      (node (ref "LCD1") (pin "14") (pinfunction "VCOMH_14") (pintype "passive"))
    )
    (net (code "62") (name "Net-(LED1-K)") (class "Default")
      (node (ref "LED1") (pin "2") (pinfunction "K_2") (pintype "passive"))
      (node (ref "R4") (pin "2") (pinfunction "2_2") (pintype "passive"))
    )
    (net (code "63") (name "Net-(Q1-G)") (class "Default")
      (node (ref "Q1") (pin "1") (pinfunction "G_1") (pintype "passive"))
      (node (ref "Q2") (pin "3") (pinfunction "D_3") (pintype "passive"))
      (node (ref "R7") (pin "1") (pinfunction "1_1") (pintype "passive"))
      (node (ref "VD2") (pin "1") (pinfunction "1_1") (pintype "passive"))
    )
    (net (code "64") (name "Net-(Q3-B-Pad2)") (class "Default")
      (node (ref "Q3") (pin "2") (pinfunction "B_2") (pintype "passive"))
      (node (ref "R20") (pin "2") (pinfunction "2_2") (pintype "passive"))
    )
    (net (code "65") (name "Net-(Q3-B-Pad5)") (class "Default")
      (node (ref "Q3") (pin "5") (pinfunction "B_5") (pintype "passive"))
      (node (ref "R15") (pin "1") (pinfunction "1_1") (pintype "passive"))
    )
    (net (code "66") (name "Net-(Q3-C-Pad3)") (class "Default")
      (node (ref "Q3") (pin "3") (pinfunction "C_3") (pintype "passive"))
      (node (ref "R16") (pin "2") (pinfunction "2_2") (pintype "passive"))
    )
    (net (code "67") (name "Net-(R22-Pad2)") (class "Default")
      (node (ref "R22") (pin "2") (pinfunction "2_2") (pintype "passive"))
      (node (ref "SJ2") (pin "2") (pinfunction "2_2") (pintype "passive"))
    )
    (net (code "68") (name "Net-(R23-Pad2)") (class "Default")
      (node (ref "R23") (pin "2") (pinfunction "2_2") (pintype "passive"))
      (node (ref "SJ3") (pin "2") (pinfunction "2_2") (pintype "passive"))
    )
    (net (code "69") (name "Net-(R31-Pad2)") (class "Default")
      (node (ref "R31") (pin "2") (pinfunction "2_2") (pintype "passive"))
      (node (ref "SJ4") (pin "2") (pinfunction "2_2") (pintype "passive"))
    )
    (net (code "70") (name "Net-(U1-PROG)") (class "Default")
      (node (ref "R1") (pin "2") (pinfunction "2_2") (pintype "passive"))
      (node (ref "U1") (pin "5") (pinfunction "PROG_5") (pintype "passive"))
    )
    (net (code "71") (name "Net-(U3-EN)") (class "Default")
      (node (ref "C4") (pin "1") (pinfunction "1_1") (pintype "passive"))
      (node (ref "R3") (pin "1") (pinfunction "1_1") (pintype "passive"))
      (node (ref "U3") (pin "6") (pinfunction "EN_6") (pintype "input"))
      (node (ref "U3") (pin "8") (pinfunction "VINA_8") (pintype "passive"))
    )
    (net (code "72") (name "Net-(U3-L1)") (class "Default")
      (node (ref "L1") (pin "1") (pintype "passive"))
      (node (ref "U3") (pin "4") (pinfunction "L1_4") (pintype "passive"))
    )
    (net (code "73") (name "Net-(U3-L2)") (class "Default")
      (node (ref "L1") (pin "2") (pinfunction "2_2") (pintype "passive"))
      (node (ref "U3") (pin "2") (pinfunction "L2_2") (pintype "passive"))
    )
    (net (code "74") (name "Net-(U4-V3)") (class "Default")
      (node (ref "C18") (pin "1") (pinfunction "1_1") (pintype "passive"))
      (node (ref "U4") (pin "6") (pinfunction "V3_6") (pintype "passive"))
    )
    (net (code "75") (name "Net-(X1-OUT)") (class "Default")
      (node (ref "R27") (pin "2") (pinfunction "2_2") (pintype "passive"))
      (node (ref "X1") (pin "3") (pinfunction "OUT_3") (pintype "output"))
    )
    (net (code "76") (name "Net-(X1-~{ST})") (class "Default")
      (node (ref "R28") (pin "1") (pinfunction "1_1") (pintype "passive"))
      (node (ref "X1") (pin "1") (pinfunction "~{ST}_1") (pintype "passive"))
    )
    (net (code "77") (name "VUSB") (class "Default")
      (node (ref "F1") (pin "1") (pinfunction "1_1") (pintype "passive"))
      (node (ref "USB1") (pin "A4") (pinfunction "VBUS_A4") (pintype "passive"))
      (node (ref "USB1") (pin "A9") (pinfunction "VBUS_A9") (pintype "passive"))
      (node (ref "USB1") (pin "B4") (pinfunction "VBUS_B4") (pintype "passive"))
      (node (ref "USB1") (pin "B9") (pinfunction "VBUS_B9") (pintype "passive"))
    )
    (net (code "78") (name "unconnected-(U2-ADC1-Pad16)") (class "Default")
      (node (ref "U2") (pin "16") (pinfunction "ADC1_16") (pintype "input+no_connect"))
    )
    (net (code "79") (name "unconnected-(U2-ADC2-Pad15)") (class "Default")
      (node (ref "U2") (pin "15") (pinfunction "ADC2_15") (pintype "input+no_connect"))
    )
    (net (code "80") (name "unconnected-(U2-ADC3-Pad13)") (class "Default")
      (node (ref "U2") (pin "13") (pinfunction "ADC3_13") (pintype "input+no_connect"))
    )
    (net (code "81") (name "unconnected-(U2-NC-Pad2)") (class "Default")
      (node (ref "U2") (pin "2") (pinfunction "NC_2") (pintype "power_in+no_connect"))
    )
    (net (code "82") (name "unconnected-(U2-NC-Pad3)") (class "Default")
      (node (ref "U2") (pin "3") (pinfunction "NC_3") (pintype "power_in+no_connect"))
    )
    (net (code "83") (name "unconnected-(U2-SA0{slash}SDO-Pad7)") (class "Default")
      (node (ref "U2") (pin "7") (pinfunction "SA0/SDO_7") (pintype "bidirectional+no_connect"))
    )
    (net (code "84") (name "unconnected-(U2-~{CS}{slash}MODE-Pad8)") (class "Default")
      (node (ref "U2") (pin "8") (pinfunction "~{CS}/MODE_8") (pintype "input+no_connect"))
    )
    (net (code "85") (name "unconnected-(U4-ACT#-Pad10)") (class "Default")
      (node (ref "U4") (pin "10") (pinfunction "ACT#_10") (pintype "passive+no_connect"))
    )
    (net (code "86") (name "unconnected-(U4-CTS-Pad15)") (class "Default")
      (node (ref "U4") (pin "15") (pinfunction "CTS_15") (pintype "passive+no_connect"))
    )
    (net (code "87") (name "unconnected-(U4-DCD-Pad11)") (class "Default")
      (node (ref "U4") (pin "11") (pinfunction "DCD_11") (pintype "passive+no_connect"))
    )
    (net (code "88") (name "unconnected-(U4-DSR-Pad14)") (class "Default")
      (node (ref "U4") (pin "14") (pinfunction "DSR_14") (pintype "passive+no_connect"))
    )
    (net (code "89") (name "unconnected-(U4-RI-Pad16)") (class "Default")
      (node (ref "U4") (pin "16") (pinfunction "RI_16") (pintype "passive+no_connect"))
    )
  )
)
